# Sheet1.net
KiCad netlist of a schematic drawn in Altium Designer
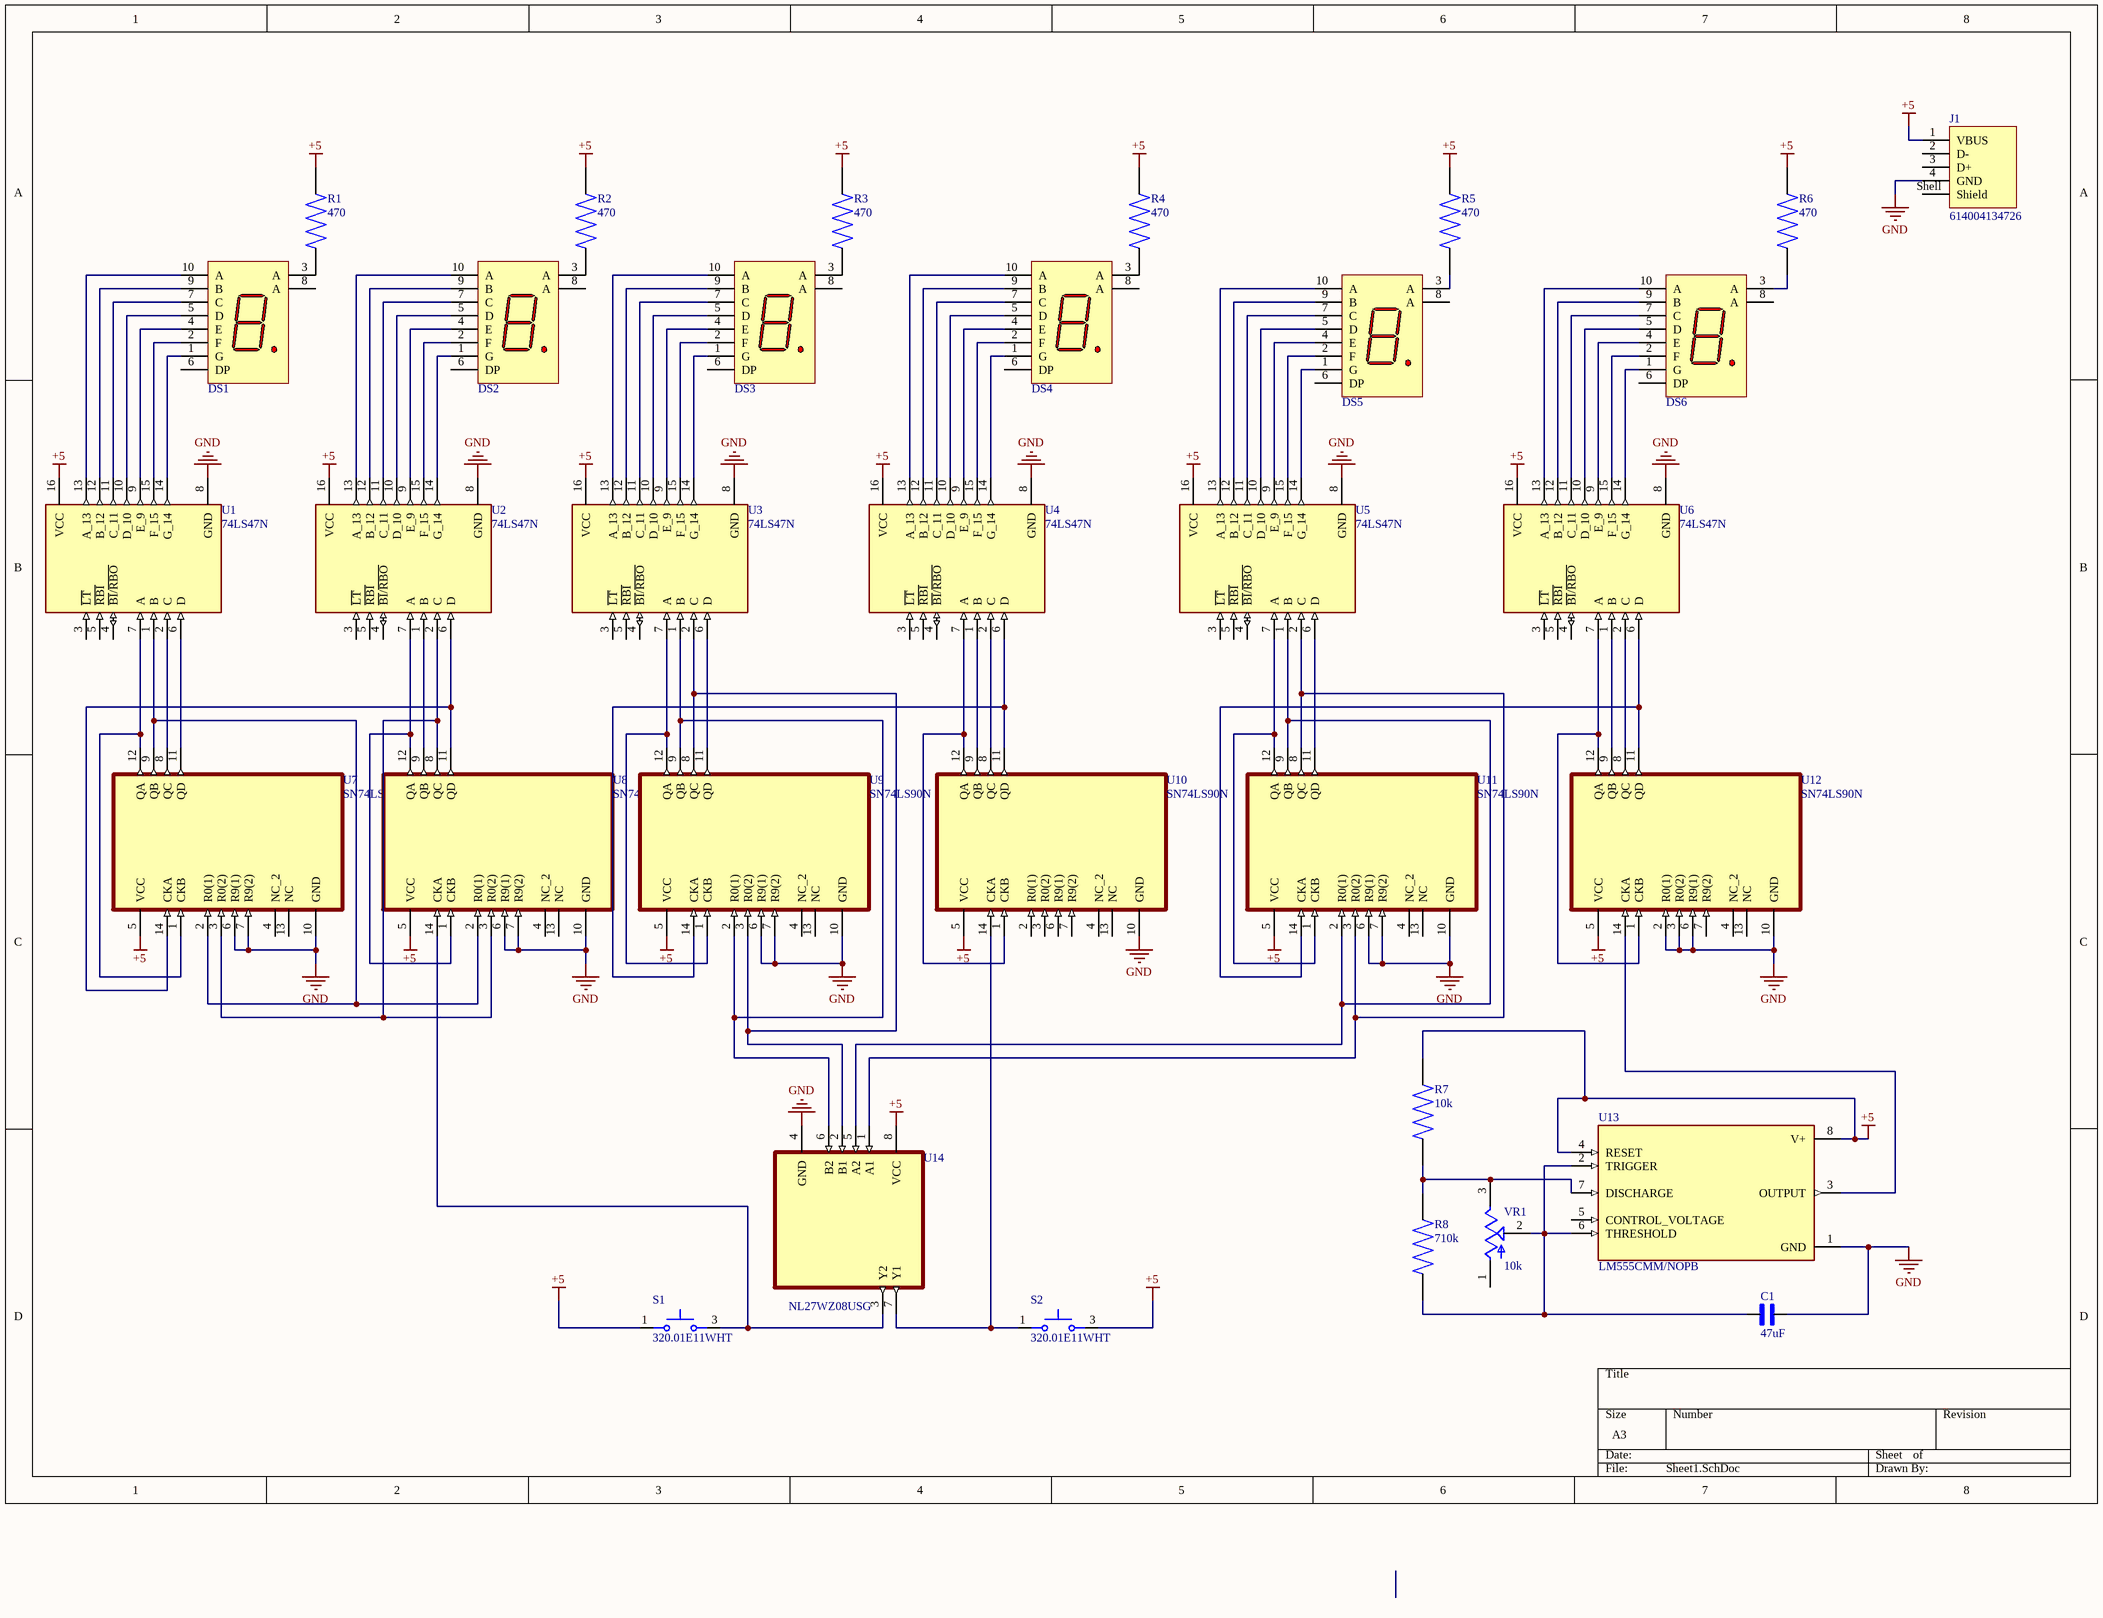
[diagram p0: Sheet1.SchDoc]

(export (version "E")
  (design (tool "Eeschema 10.0.6"))
  (components
    (comp (ref "C1")
      (value "47uF")
      (footprint "CAPC1608X90N")
      (description "Capacitor MLCC 0603 100nF 16V ¦ AVX 0603YC104KAZ2A")
      (fields (field (name "MF") "AVX") (field (name "MP") "0603YC104KAZ2A"))
      (libsource (lib "0603YC104KAZ2A") (part "0603YC104KAZ2A"))
    )
    (comp (ref "DS1")
      (value "157119S12801")
      (footprint "WL-T7DS_L13W10H7")
      (description "WL-T7DS 7 Segments Display THT Single Digit, 0.39\"/ 9.9mm, Common Anode, 38mcd, 2V, Super Red")
      (fields (field (name "MANUFACTURER") "Wurth Elektronik"))
      (libsource (lib "WL-T7DS") (part "157119S12801"))
    )
    (comp (ref "DS2")
      (value "157119S12801")
      (footprint "WL-T7DS_L13W10H7")
      (description "WL-T7DS 7 Segments Display THT Single Digit, 0.39\"/ 9.9mm, Common Anode, 38mcd, 2V, Super Red")
      (fields (field (name "MANUFACTURER") "Wurth Elektronik"))
      (libsource (lib "WL-T7DS") (part "157119S12801"))
    )
    (comp (ref "DS3")
      (value "157119S12801")
      (footprint "WL-T7DS_L13W10H7")
      (description "WL-T7DS 7 Segments Display THT Single Digit, 0.39\"/ 9.9mm, Common Anode, 38mcd, 2V, Super Red")
      (fields (field (name "MANUFACTURER") "Wurth Elektronik"))
      (libsource (lib "WL-T7DS") (part "157119S12801"))
    )
    (comp (ref "DS4")
      (value "157119S12801")
      (footprint "WL-T7DS_L13W10H7")
      (description "WL-T7DS 7 Segments Display THT Single Digit, 0.39\"/ 9.9mm, Common Anode, 38mcd, 2V, Super Red")
      (fields (field (name "MANUFACTURER") "Wurth Elektronik"))
      (libsource (lib "WL-T7DS") (part "157119S12801"))
    )
    (comp (ref "DS5")
      (value "157119S12801")
      (footprint "WL-T7DS_L13W10H7")
      (description "WL-T7DS 7 Segments Display THT Single Digit, 0.39\"/ 9.9mm, Common Anode, 38mcd, 2V, Super Red")
      (fields (field (name "MANUFACTURER") "Wurth Elektronik"))
      (libsource (lib "WL-T7DS") (part "157119S12801"))
    )
    (comp (ref "DS6")
      (value "157119S12801")
      (footprint "WL-T7DS_L13W10H7")
      (description "WL-T7DS 7 Segments Display THT Single Digit, 0.39\"/ 9.9mm, Common Anode, 38mcd, 2V, Super Red")
      (fields (field (name "MANUFACTURER") "Wurth Elektronik"))
      (libsource (lib "WL-T7DS") (part "157119S12801"))
    )
    (comp (ref "J1")
      (value "614004134726")
      (footprint "614004134726")
      (description "WR-COM USB 2.0 Type A Up Right")
      (fields (field (name "MANUFACTURER") "Wurth Elektronik"))
      (libsource (lib "WR-USB") (part "614004134726"))
    )
    (comp (ref "R1")
      (value "470")
      (footprint "RES_ERJU01F2202C:RES_ERJU01F2202C")
      (fields (field (name "MP") "ERJU01F2202C"))
      (libsource (lib "ERJU01F2202C") (part "ERJU01F2202C"))
    )
    (comp (ref "R2")
      (value "470")
      (footprint "RES_ERJU01F2202C:RES_ERJU01F2202C")
      (fields (field (name "MP") "ERJU01F2202C"))
      (libsource (lib "ERJU01F2202C") (part "ERJU01F2202C"))
    )
    (comp (ref "R3")
      (value "470")
      (footprint "RES_ERJU01F2202C:RES_ERJU01F2202C")
      (fields (field (name "MP") "ERJU01F2202C"))
      (libsource (lib "ERJU01F2202C") (part "ERJU01F2202C"))
    )
    (comp (ref "R4")
      (value "470")
      (footprint "RES_ERJU01F2202C:RES_ERJU01F2202C")
      (fields (field (name "MP") "ERJU01F2202C"))
      (libsource (lib "ERJU01F2202C") (part "ERJU01F2202C"))
    )
    (comp (ref "R5")
      (value "470")
      (footprint "RES_ERJU01F2202C:RES_ERJU01F2202C")
      (fields (field (name "MP") "ERJU01F2202C"))
      (libsource (lib "ERJU01F2202C") (part "ERJU01F2202C"))
    )
    (comp (ref "R6")
      (value "470")
      (footprint "RES_ERJU01F2202C:RES_ERJU01F2202C")
      (fields (field (name "MP") "ERJU01F2202C"))
      (libsource (lib "ERJU01F2202C") (part "ERJU01F2202C"))
    )
    (comp (ref "R7")
      (value "10k")
      (footprint "RES_ERJU01F2202C:RES_ERJU01F2202C")
      (fields (field (name "MP") "ERJU01F2202C"))
      (libsource (lib "ERJU01F2202C") (part "ERJU01F2202C"))
    )
    (comp (ref "R8")
      (value "710k")
      (footprint "RES_ERJU01F2202C:RES_ERJU01F2202C")
      (fields (field (name "MP") "ERJU01F2202C"))
      (libsource (lib "ERJU01F2202C") (part "ERJU01F2202C"))
    )
    (comp (ref "S1")
      (value "320.01E11WHT")
      (footprint "SW_320.01E11WHT")
      (description "PUSHBUTTON, 25mA, 50VDC SPST-NO, Off-(On) Through Hole")
      (fields (field (name "MF") "E-Switch"))
      (libsource (lib "320.01E11WHT") (part "320.01E11WHT"))
    )
    (comp (ref "S2")
      (value "320.01E11WHT")
      (footprint "SW_320.01E11WHT")
      (description "PUSHBUTTON, 25mA, 50VDC SPST-NO, Off-(On) Through Hole")
      (fields (field (name "MF") "E-Switch"))
      (libsource (lib "320.01E11WHT") (part "320.01E11WHT"))
    )
    (comp (ref "U1")
      (value "74LS47N")
      (footprint "DIP794W45P254L1930H508Q16")
      (description "IC DRVR BCD-7 SEGMENT 16SO")
      (fields (field (name "MF") "Texas Instruments"))
      (libsource (lib "74LS47N") (part "74LS47N"))
    )
    (comp (ref "U2")
      (value "74LS47N")
      (footprint "DIP794W45P254L1930H508Q16")
      (description "IC DRVR BCD-7 SEGMENT 16SO")
      (fields (field (name "MF") "Texas Instruments"))
      (libsource (lib "74LS47N") (part "74LS47N"))
    )
    (comp (ref "U3")
      (value "74LS47N")
      (footprint "DIP794W45P254L1930H508Q16")
      (description "IC DRVR BCD-7 SEGMENT 16SO")
      (fields (field (name "MF") "Texas Instruments"))
      (libsource (lib "74LS47N") (part "74LS47N"))
    )
    (comp (ref "U4")
      (value "74LS47N")
      (footprint "DIP794W45P254L1930H508Q16")
      (description "IC DRVR BCD-7 SEGMENT 16SO")
      (fields (field (name "MF") "Texas Instruments"))
      (libsource (lib "74LS47N") (part "74LS47N"))
    )
    (comp (ref "U5")
      (value "74LS47N")
      (footprint "DIP794W45P254L1930H508Q16")
      (description "IC DRVR BCD-7 SEGMENT 16SO")
      (fields (field (name "MF") "Texas Instruments"))
      (libsource (lib "74LS47N") (part "74LS47N"))
    )
    (comp (ref "U6")
      (value "74LS47N")
      (footprint "DIP794W45P254L1930H508Q16")
      (description "IC DRVR BCD-7 SEGMENT 16SO")
      (fields (field (name "MF") "Texas Instruments"))
      (libsource (lib "74LS47N") (part "74LS47N"))
    )
    (comp (ref "U7")
      (value "SN74LS90N")
      (footprint "DIP254P762X508-14")
      (description "Counter IC Counter, Decade 1 Element 4 Bit Negative Edge 14-SOIC")
      (fields (field (name "MF") "Texas Instruments") (field (name "MP") "74LS90"))
      (libsource (lib "SN74LS90N") (part "SN74LS90N"))
    )
    (comp (ref "U8")
      (value "SN74LS90N")
      (footprint "DIP254P762X508-14")
      (description "Counter IC Counter, Decade 1 Element 4 Bit Negative Edge 14-SOIC")
      (fields (field (name "MF") "Texas Instruments") (field (name "MP") "74LS90"))
      (libsource (lib "SN74LS90N") (part "SN74LS90N"))
    )
    (comp (ref "U9")
      (value "SN74LS90N")
      (footprint "DIP254P762X508-14")
      (description "Counter IC Counter, Decade 1 Element 4 Bit Negative Edge 14-SOIC")
      (fields (field (name "MF") "Texas Instruments") (field (name "MP") "74LS90"))
      (libsource (lib "SN74LS90N") (part "SN74LS90N"))
    )
    (comp (ref "U10")
      (value "SN74LS90N")
      (footprint "DIP254P762X508-14")
      (description "Counter IC Counter, Decade 1 Element 4 Bit Negative Edge 14-SOIC")
      (fields (field (name "MF") "Texas Instruments") (field (name "MP") "74LS90"))
      (libsource (lib "SN74LS90N") (part "SN74LS90N"))
    )
    (comp (ref "U11")
      (value "SN74LS90N")
      (footprint "DIP254P762X508-14")
      (description "Counter IC Counter, Decade 1 Element 4 Bit Negative Edge 14-SOIC")
      (fields (field (name "MF") "Texas Instruments") (field (name "MP") "74LS90"))
      (libsource (lib "SN74LS90N") (part "SN74LS90N"))
    )
    (comp (ref "U12")
      (value "SN74LS90N")
      (footprint "DIP254P762X508-14")
      (description "Counter IC Counter, Decade 1 Element 4 Bit Negative Edge 14-SOIC")
      (fields (field (name "MF") "Texas Instruments") (field (name "MP") "74LS90"))
      (libsource (lib "SN74LS90N") (part "SN74LS90N"))
    )
    (comp (ref "U13")
      (value "LM555CMM/NOPB")
      (footprint "SOP65P490X110-8N")
      (description "Highly Stable 555 Timer")
      (fields (field (name "MF") "Texas Instruments"))
      (libsource (lib "LM555CMM_NOPB") (part "LM555CMM/NOPB"))
    )
    (comp (ref "U14")
      (value "NL27WZ08USG")
      (footprint "SOP50P310X90-8N")
      (description "NL27WZ08USG, Dual 2-Input AND Logic Gate, 1.65 - 5.5 V, 8-Pin US ¦ ON Semiconductor NL27WZ08USG")
      (fields (field (name "MF") "ON Semiconductor"))
      (libsource (lib "NL27WZ08USG") (part "NL27WZ08USG"))
    )
    (comp (ref "VR1")
      (value "10k")
      (footprint "TRIM_3362P-1-223LF")
      (fields
        (field (name "MF") "Bourns Electronics")
        (field (name "MP") "3362P1223LF")
        (field (name "Comment") "3362P-1-223LF")
      )
      (libsource (lib "3362P-1-223LF") (part "3362P-1-223LF"))
    )
  )
  (nets
    (net (code "1") (name "+5") (class "Default")
      (node (ref "J1") (pin "1") (pinfunction "VBUS_1") (pintype "passive"))
      (node (ref "R1") (pin "2") (pinfunction "2_2") (pintype "passive"))
      (node (ref "R2") (pin "2") (pinfunction "2_2") (pintype "passive"))
      (node (ref "R3") (pin "2") (pinfunction "2_2") (pintype "passive"))
      (node (ref "R4") (pin "2") (pinfunction "2_2") (pintype "passive"))
      (node (ref "R5") (pin "2") (pinfunction "2_2") (pintype "passive"))
      (node (ref "R6") (pin "2") (pinfunction "2_2") (pintype "passive"))
      (node (ref "R7") (pin "2") (pinfunction "2_2") (pintype "passive"))
      (node (ref "S1") (pin "1") (pinfunction "1_1") (pintype "passive"))
      (node (ref "S2") (pin "3") (pinfunction "3_3") (pintype "passive"))
      (node (ref "U1") (pin "16") (pinfunction "VCC_16") (pintype "power_in"))
      (node (ref "U10") (pin "5") (pinfunction "VCC_5") (pintype "power_in"))
      (node (ref "U11") (pin "5") (pinfunction "VCC_5") (pintype "power_in"))
      (node (ref "U12") (pin "5") (pinfunction "VCC_5") (pintype "power_in"))
      (node (ref "U13") (pin "4") (pinfunction "RESET_4") (pintype "input"))
      (node (ref "U13") (pin "8") (pinfunction "V+_8") (pintype "power_in"))
      (node (ref "U14") (pin "8") (pinfunction "VCC_8") (pintype "power_in"))
      (node (ref "U2") (pin "16") (pinfunction "VCC_16") (pintype "power_in"))
      (node (ref "U3") (pin "16") (pinfunction "VCC_16") (pintype "power_in"))
      (node (ref "U4") (pin "16") (pinfunction "VCC_16") (pintype "power_in"))
      (node (ref "U5") (pin "16") (pinfunction "VCC_16") (pintype "power_in"))
      (node (ref "U6") (pin "16") (pinfunction "VCC_16") (pintype "power_in"))
      (node (ref "U7") (pin "5") (pinfunction "VCC_5") (pintype "power_in"))
      (node (ref "U8") (pin "5") (pinfunction "VCC_5") (pintype "power_in"))
      (node (ref "U9") (pin "5") (pinfunction "VCC_5") (pintype "power_in"))
    )
    (net (code "2") (name "GND") (class "Default")
      (node (ref "C1") (pin "2") (pinfunction "2_2") (pintype "passive"))
      (node (ref "J1") (pin "4") (pinfunction "GND_4") (pintype "passive"))
      (node (ref "U1") (pin "8") (pinfunction "GND_8") (pintype "power_in"))
      (node (ref "U10") (pin "10") (pinfunction "GND_10") (pintype "passive"))
      (node (ref "U11") (pin "10") (pinfunction "GND_10") (pintype "passive"))
      (node (ref "U11") (pin "6") (pinfunction "R9(1)_6") (pintype "input"))
      (node (ref "U11") (pin "7") (pinfunction "R9(2)_7") (pintype "input"))
      (node (ref "U12") (pin "10") (pinfunction "GND_10") (pintype "passive"))
      (node (ref "U12") (pin "2") (pinfunction "R0(1)_2") (pintype "input"))
      (node (ref "U12") (pin "3") (pinfunction "R0(2)_3") (pintype "input"))
      (node (ref "U12") (pin "6") (pinfunction "R9(1)_6") (pintype "input"))
      (node (ref "U13") (pin "1") (pinfunction "GND_1") (pintype "power_in"))
      (node (ref "U14") (pin "4") (pinfunction "GND_4") (pintype "passive"))
      (node (ref "U2") (pin "8") (pinfunction "GND_8") (pintype "power_in"))
      (node (ref "U3") (pin "8") (pinfunction "GND_8") (pintype "power_in"))
      (node (ref "U4") (pin "8") (pinfunction "GND_8") (pintype "power_in"))
      (node (ref "U5") (pin "8") (pinfunction "GND_8") (pintype "power_in"))
      (node (ref "U6") (pin "8") (pinfunction "GND_8") (pintype "power_in"))
      (node (ref "U7") (pin "10") (pinfunction "GND_10") (pintype "passive"))
      (node (ref "U7") (pin "6") (pinfunction "R9(1)_6") (pintype "input"))
      (node (ref "U7") (pin "7") (pinfunction "R9(2)_7") (pintype "input"))
      (node (ref "U8") (pin "10") (pinfunction "GND_10") (pintype "passive"))
      (node (ref "U8") (pin "6") (pinfunction "R9(1)_6") (pintype "input"))
      (node (ref "U8") (pin "7") (pinfunction "R9(2)_7") (pintype "input"))
      (node (ref "U9") (pin "10") (pinfunction "GND_10") (pintype "passive"))
      (node (ref "U9") (pin "6") (pinfunction "R9(1)_6") (pintype "input"))
      (node (ref "U9") (pin "7") (pinfunction "R9(2)_7") (pintype "input"))
    )
    (net (code "3") (name "Net-(DS1-A-Pad3)") (class "Default")
      (node (ref "DS1") (pin "3") (pinfunction "A_3") (pintype "passive"))
      (node (ref "R1") (pin "1") (pinfunction "1_1") (pintype "passive"))
    )
    (net (code "4") (name "Net-(DS1-B)") (class "Default")
      (node (ref "DS1") (pin "9") (pinfunction "B_9") (pintype "passive"))
      (node (ref "U1") (pin "12") (pinfunction "B_12_12") (pintype "output"))
    )
    (net (code "5") (name "Net-(DS1-C)") (class "Default")
      (node (ref "DS1") (pin "7") (pinfunction "C_7") (pintype "passive"))
      (node (ref "U1") (pin "11") (pinfunction "C_11_11") (pintype "output"))
    )
    (net (code "6") (name "Net-(DS1-D)") (class "Default")
      (node (ref "DS1") (pin "5") (pinfunction "D_5") (pintype "passive"))
      (node (ref "U1") (pin "10") (pinfunction "D_10_10") (pintype "output"))
    )
    (net (code "7") (name "Net-(DS1-E)") (class "Default")
      (node (ref "DS1") (pin "4") (pinfunction "E_4") (pintype "passive"))
      (node (ref "U1") (pin "9") (pinfunction "E_9_9") (pintype "output"))
    )
    (net (code "8") (name "Net-(DS1-F)") (class "Default")
      (node (ref "DS1") (pin "2") (pinfunction "F_2") (pintype "passive"))
      (node (ref "U1") (pin "15") (pinfunction "F_15_15") (pintype "output"))
    )
    (net (code "9") (name "Net-(DS1-G)") (class "Default")
      (node (ref "DS1") (pin "1") (pinfunction "G_1") (pintype "passive"))
      (node (ref "U1") (pin "14") (pinfunction "G_14_14") (pintype "output"))
    )
    (net (code "10") (name "Net-(DS2-A-Pad3)") (class "Default")
      (node (ref "DS2") (pin "3") (pinfunction "A_3") (pintype "passive"))
      (node (ref "R2") (pin "1") (pinfunction "1_1") (pintype "passive"))
    )
    (net (code "11") (name "Net-(DS2-B)") (class "Default")
      (node (ref "DS2") (pin "9") (pinfunction "B_9") (pintype "passive"))
      (node (ref "U2") (pin "12") (pinfunction "B_12_12") (pintype "output"))
    )
    (net (code "12") (name "Net-(DS2-C)") (class "Default")
      (node (ref "DS2") (pin "7") (pinfunction "C_7") (pintype "passive"))
      (node (ref "U2") (pin "11") (pinfunction "C_11_11") (pintype "output"))
    )
    (net (code "13") (name "Net-(DS2-D)") (class "Default")
      (node (ref "DS2") (pin "5") (pinfunction "D_5") (pintype "passive"))
      (node (ref "U2") (pin "10") (pinfunction "D_10_10") (pintype "output"))
    )
    (net (code "14") (name "Net-(DS2-E)") (class "Default")
      (node (ref "DS2") (pin "4") (pinfunction "E_4") (pintype "passive"))
      (node (ref "U2") (pin "9") (pinfunction "E_9_9") (pintype "output"))
    )
    (net (code "15") (name "Net-(DS2-F)") (class "Default")
      (node (ref "DS2") (pin "2") (pinfunction "F_2") (pintype "passive"))
      (node (ref "U2") (pin "15") (pinfunction "F_15_15") (pintype "output"))
    )
    (net (code "16") (name "Net-(DS2-G)") (class "Default")
      (node (ref "DS2") (pin "1") (pinfunction "G_1") (pintype "passive"))
      (node (ref "U2") (pin "14") (pinfunction "G_14_14") (pintype "output"))
    )
    (net (code "17") (name "Net-(DS3-A-Pad3)") (class "Default")
      (node (ref "DS3") (pin "3") (pinfunction "A_3") (pintype "passive"))
      (node (ref "R3") (pin "1") (pinfunction "1_1") (pintype "passive"))
    )
    (net (code "18") (name "Net-(DS3-B)") (class "Default")
      (node (ref "DS3") (pin "9") (pinfunction "B_9") (pintype "passive"))
      (node (ref "U3") (pin "12") (pinfunction "B_12_12") (pintype "output"))
    )
    (net (code "19") (name "Net-(DS3-C)") (class "Default")
      (node (ref "DS3") (pin "7") (pinfunction "C_7") (pintype "passive"))
      (node (ref "U3") (pin "11") (pinfunction "C_11_11") (pintype "output"))
    )
    (net (code "20") (name "Net-(DS3-D)") (class "Default")
      (node (ref "DS3") (pin "5") (pinfunction "D_5") (pintype "passive"))
      (node (ref "U3") (pin "10") (pinfunction "D_10_10") (pintype "output"))
    )
    (net (code "21") (name "Net-(DS3-E)") (class "Default")
      (node (ref "DS3") (pin "4") (pinfunction "E_4") (pintype "passive"))
      (node (ref "U3") (pin "9") (pinfunction "E_9_9") (pintype "output"))
    )
    (net (code "22") (name "Net-(DS3-F)") (class "Default")
      (node (ref "DS3") (pin "2") (pinfunction "F_2") (pintype "passive"))
      (node (ref "U3") (pin "15") (pinfunction "F_15_15") (pintype "output"))
    )
    (net (code "23") (name "Net-(DS3-G)") (class "Default")
      (node (ref "DS3") (pin "1") (pinfunction "G_1") (pintype "passive"))
      (node (ref "U3") (pin "14") (pinfunction "G_14_14") (pintype "output"))
    )
    (net (code "24") (name "Net-(DS4-A-Pad3)") (class "Default")
      (node (ref "DS4") (pin "3") (pinfunction "A_3") (pintype "passive"))
      (node (ref "R4") (pin "1") (pinfunction "1_1") (pintype "passive"))
    )
    (net (code "25") (name "Net-(DS4-B)") (class "Default")
      (node (ref "DS4") (pin "9") (pinfunction "B_9") (pintype "passive"))
      (node (ref "U4") (pin "12") (pinfunction "B_12_12") (pintype "output"))
    )
    (net (code "26") (name "Net-(DS4-C)") (class "Default")
      (node (ref "DS4") (pin "7") (pinfunction "C_7") (pintype "passive"))
      (node (ref "U4") (pin "11") (pinfunction "C_11_11") (pintype "output"))
    )
    (net (code "27") (name "Net-(DS4-D)") (class "Default")
      (node (ref "DS4") (pin "5") (pinfunction "D_5") (pintype "passive"))
      (node (ref "U4") (pin "10") (pinfunction "D_10_10") (pintype "output"))
    )
    (net (code "28") (name "Net-(DS4-E)") (class "Default")
      (node (ref "DS4") (pin "4") (pinfunction "E_4") (pintype "passive"))
      (node (ref "U4") (pin "9") (pinfunction "E_9_9") (pintype "output"))
    )
    (net (code "29") (name "Net-(DS4-F)") (class "Default")
      (node (ref "DS4") (pin "2") (pinfunction "F_2") (pintype "passive"))
      (node (ref "U4") (pin "15") (pinfunction "F_15_15") (pintype "output"))
    )
    (net (code "30") (name "Net-(DS4-G)") (class "Default")
      (node (ref "DS4") (pin "1") (pinfunction "G_1") (pintype "passive"))
      (node (ref "U4") (pin "14") (pinfunction "G_14_14") (pintype "output"))
    )
    (net (code "31") (name "Net-(DS5-A-Pad3)") (class "Default")
      (node (ref "DS5") (pin "3") (pinfunction "A_3") (pintype "passive"))
      (node (ref "R5") (pin "1") (pinfunction "1_1") (pintype "passive"))
    )
    (net (code "32") (name "Net-(DS5-B)") (class "Default")
      (node (ref "DS5") (pin "9") (pinfunction "B_9") (pintype "passive"))
      (node (ref "U5") (pin "12") (pinfunction "B_12_12") (pintype "output"))
    )
    (net (code "33") (name "Net-(DS5-C)") (class "Default")
      (node (ref "DS5") (pin "7") (pinfunction "C_7") (pintype "passive"))
      (node (ref "U5") (pin "11") (pinfunction "C_11_11") (pintype "output"))
    )
    (net (code "34") (name "Net-(DS5-D)") (class "Default")
      (node (ref "DS5") (pin "5") (pinfunction "D_5") (pintype "passive"))
      (node (ref "U5") (pin "10") (pinfunction "D_10_10") (pintype "output"))
    )
    (net (code "35") (name "Net-(DS5-E)") (class "Default")
      (node (ref "DS5") (pin "4") (pinfunction "E_4") (pintype "passive"))
      (node (ref "U5") (pin "9") (pinfunction "E_9_9") (pintype "output"))
    )
    (net (code "36") (name "Net-(DS5-F)") (class "Default")
      (node (ref "DS5") (pin "2") (pinfunction "F_2") (pintype "passive"))
      (node (ref "U5") (pin "15") (pinfunction "F_15_15") (pintype "output"))
    )
    (net (code "37") (name "Net-(DS5-G)") (class "Default")
      (node (ref "DS5") (pin "1") (pinfunction "G_1") (pintype "passive"))
      (node (ref "U5") (pin "14") (pinfunction "G_14_14") (pintype "output"))
    )
    (net (code "38") (name "Net-(DS6-A-Pad3)") (class "Default")
      (node (ref "DS6") (pin "3") (pinfunction "A_3") (pintype "passive"))
      (node (ref "R6") (pin "1") (pinfunction "1_1") (pintype "passive"))
    )
    (net (code "39") (name "Net-(DS6-B)") (class "Default")
      (node (ref "DS6") (pin "9") (pinfunction "B_9") (pintype "passive"))
      (node (ref "U6") (pin "12") (pinfunction "B_12_12") (pintype "output"))
    )
    (net (code "40") (name "Net-(DS6-C)") (class "Default")
      (node (ref "DS6") (pin "7") (pinfunction "C_7") (pintype "passive"))
      (node (ref "U6") (pin "11") (pinfunction "C_11_11") (pintype "output"))
    )
    (net (code "41") (name "Net-(DS6-D)") (class "Default")
      (node (ref "DS6") (pin "5") (pinfunction "D_5") (pintype "passive"))
      (node (ref "U6") (pin "10") (pinfunction "D_10_10") (pintype "output"))
    )
    (net (code "42") (name "Net-(DS6-E)") (class "Default")
      (node (ref "DS6") (pin "4") (pinfunction "E_4") (pintype "passive"))
      (node (ref "U6") (pin "9") (pinfunction "E_9_9") (pintype "output"))
    )
    (net (code "43") (name "Net-(DS6-F)") (class "Default")
      (node (ref "DS6") (pin "2") (pinfunction "F_2") (pintype "passive"))
      (node (ref "U6") (pin "15") (pinfunction "F_15_15") (pintype "output"))
    )
    (net (code "44") (name "Net-(DS6-G)") (class "Default")
      (node (ref "DS6") (pin "1") (pinfunction "G_1") (pintype "passive"))
      (node (ref "U6") (pin "14") (pinfunction "G_14_14") (pintype "output"))
    )
    (net (code "45") (name "Net-(U1-A)") (class "Default")
      (node (ref "U1") (pin "7") (pinfunction "A_7") (pintype "input"))
      (node (ref "U7") (pin "1") (pinfunction "CKB_1") (pintype "input"))
      (node (ref "U7") (pin "12") (pinfunction "QA_12") (pintype "output"))
    )
    (net (code "46") (name "Net-(U1-A_13)") (class "Default")
      (node (ref "DS1") (pin "10") (pinfunction "A_10") (pintype "passive"))
      (node (ref "U1") (pin "13") (pinfunction "A_13_13") (pintype "output"))
    )
    (net (code "47") (name "Net-(U1-B)") (class "Default")
      (node (ref "U1") (pin "1") (pinfunction "B_1") (pintype "input"))
      (node (ref "U7") (pin "2") (pinfunction "R0(1)_2") (pintype "input"))
      (node (ref "U7") (pin "9") (pinfunction "QB_9") (pintype "output"))
      (node (ref "U8") (pin "2") (pinfunction "R0(1)_2") (pintype "input"))
    )
    (net (code "48") (name "Net-(U1-C)") (class "Default")
      (node (ref "U1") (pin "2") (pinfunction "C_2") (pintype "input"))
      (node (ref "U7") (pin "8") (pinfunction "QC_8") (pintype "output"))
    )
    (net (code "49") (name "Net-(U1-D)") (class "Default")
      (node (ref "U1") (pin "6") (pinfunction "D_6") (pintype "input"))
      (node (ref "U7") (pin "11") (pinfunction "QD_11") (pintype "output"))
    )
    (net (code "50") (name "Net-(U2-A)") (class "Default")
      (node (ref "U2") (pin "7") (pinfunction "A_7") (pintype "input"))
      (node (ref "U8") (pin "1") (pinfunction "CKB_1") (pintype "input"))
      (node (ref "U8") (pin "12") (pinfunction "QA_12") (pintype "output"))
    )
    (net (code "51") (name "Net-(U2-A_13)") (class "Default")
      (node (ref "DS2") (pin "10") (pinfunction "A_10") (pintype "passive"))
      (node (ref "U2") (pin "13") (pinfunction "A_13_13") (pintype "output"))
    )
    (net (code "52") (name "Net-(U2-B)") (class "Default")
      (node (ref "U2") (pin "1") (pinfunction "B_1") (pintype "input"))
      (node (ref "U8") (pin "9") (pinfunction "QB_9") (pintype "output"))
    )
    (net (code "53") (name "Net-(U2-C)") (class "Default")
      (node (ref "U2") (pin "2") (pinfunction "C_2") (pintype "input"))
      (node (ref "U7") (pin "3") (pinfunction "R0(2)_3") (pintype "input"))
      (node (ref "U8") (pin "3") (pinfunction "R0(2)_3") (pintype "input"))
      (node (ref "U8") (pin "8") (pinfunction "QC_8") (pintype "output"))
    )
    (net (code "54") (name "Net-(U2-D)") (class "Default")
      (node (ref "U2") (pin "6") (pinfunction "D_6") (pintype "input"))
      (node (ref "U7") (pin "14") (pinfunction "CKA_14") (pintype "input"))
      (node (ref "U8") (pin "11") (pinfunction "QD_11") (pintype "output"))
    )
    (net (code "55") (name "Net-(U3-A)") (class "Default")
      (node (ref "U3") (pin "7") (pinfunction "A_7") (pintype "input"))
      (node (ref "U9") (pin "1") (pinfunction "CKB_1") (pintype "input"))
      (node (ref "U9") (pin "12") (pinfunction "QA_12") (pintype "output"))
    )
    (net (code "56") (name "Net-(U3-A_13)") (class "Default")
      (node (ref "DS3") (pin "10") (pinfunction "A_10") (pintype "passive"))
      (node (ref "U3") (pin "13") (pinfunction "A_13_13") (pintype "output"))
    )
    (net (code "57") (name "Net-(U3-D)") (class "Default")
      (node (ref "U3") (pin "6") (pinfunction "D_6") (pintype "input"))
      (node (ref "U9") (pin "11") (pinfunction "QD_11") (pintype "output"))
    )
    (net (code "58") (name "Net-(U4-A_13)") (class "Default")
      (node (ref "DS4") (pin "10") (pinfunction "A_10") (pintype "passive"))
      (node (ref "U4") (pin "13") (pinfunction "A_13_13") (pintype "output"))
    )
    (net (code "59") (name "Net-(U5-A_13)") (class "Default")
      (node (ref "DS5") (pin "10") (pinfunction "A_10") (pintype "passive"))
      (node (ref "U5") (pin "13") (pinfunction "A_13_13") (pintype "output"))
    )
    (net (code "60") (name "Net-(U6-A_13)") (class "Default")
      (node (ref "DS6") (pin "10") (pinfunction "A_10") (pintype "passive"))
      (node (ref "U6") (pin "13") (pinfunction "A_13_13") (pintype "output"))
    )
    (net (code "61") (name "Net-(U10-CKA)") (class "Default")
      (node (ref "S2") (pin "1") (pinfunction "1_1") (pintype "passive"))
      (node (ref "U10") (pin "14") (pinfunction "CKA_14") (pintype "input"))
      (node (ref "U14") (pin "7") (pinfunction "Y1_7") (pintype "output"))
    )
    (net (code "62") (name "Net-(U10-CKB)") (class "Default")
      (node (ref "U10") (pin "1") (pinfunction "CKB_1") (pintype "input"))
      (node (ref "U10") (pin "12") (pinfunction "QA_12") (pintype "output"))
      (node (ref "U4") (pin "7") (pinfunction "A_7") (pintype "input"))
    )
    (net (code "63") (name "Net-(U10-QB)") (class "Default")
      (node (ref "U10") (pin "9") (pinfunction "QB_9") (pintype "output"))
      (node (ref "U4") (pin "1") (pinfunction "B_1") (pintype "input"))
    )
    (net (code "64") (name "Net-(U10-QC)") (class "Default")
      (node (ref "U10") (pin "8") (pinfunction "QC_8") (pintype "output"))
      (node (ref "U4") (pin "2") (pinfunction "C_2") (pintype "input"))
    )
    (net (code "65") (name "Net-(U10-QD)") (class "Default")
      (node (ref "U10") (pin "11") (pinfunction "QD_11") (pintype "output"))
      (node (ref "U4") (pin "6") (pinfunction "D_6") (pintype "input"))
      (node (ref "U9") (pin "14") (pinfunction "CKA_14") (pintype "input"))
    )
    (net (code "66") (name "Net-(U11-CKA)") (class "Default")
      (node (ref "U11") (pin "14") (pinfunction "CKA_14") (pintype "input"))
      (node (ref "U12") (pin "11") (pinfunction "QD_11") (pintype "output"))
      (node (ref "U6") (pin "6") (pinfunction "D_6") (pintype "input"))
    )
    (net (code "67") (name "Net-(U11-CKB)") (class "Default")
      (node (ref "U11") (pin "1") (pinfunction "CKB_1") (pintype "input"))
      (node (ref "U11") (pin "12") (pinfunction "QA_12") (pintype "output"))
      (node (ref "U5") (pin "7") (pinfunction "A_7") (pintype "input"))
    )
    (net (code "68") (name "Net-(U11-QB)") (class "Default")
      (node (ref "U11") (pin "2") (pinfunction "R0(1)_2") (pintype "input"))
      (node (ref "U11") (pin "9") (pinfunction "QB_9") (pintype "output"))
      (node (ref "U14") (pin "5") (pinfunction "A2_5") (pintype "input"))
      (node (ref "U5") (pin "1") (pinfunction "B_1") (pintype "input"))
    )
    (net (code "69") (name "Net-(U11-QC)") (class "Default")
      (node (ref "U11") (pin "3") (pinfunction "R0(2)_3") (pintype "input"))
      (node (ref "U11") (pin "8") (pinfunction "QC_8") (pintype "output"))
      (node (ref "U14") (pin "1") (pinfunction "A1_1") (pintype "input"))
      (node (ref "U5") (pin "2") (pinfunction "C_2") (pintype "input"))
    )
    (net (code "70") (name "Net-(U11-QD)") (class "Default")
      (node (ref "U11") (pin "11") (pinfunction "QD_11") (pintype "output"))
      (node (ref "U5") (pin "6") (pinfunction "D_6") (pintype "input"))
    )
    (net (code "71") (name "Net-(U12-CKA)") (class "Default")
      (node (ref "U12") (pin "14") (pinfunction "CKA_14") (pintype "input"))
      (node (ref "U13") (pin "3") (pinfunction "OUTPUT_3") (pintype "output"))
    )
    (net (code "72") (name "Net-(U12-CKB)") (class "Default")
      (node (ref "U12") (pin "1") (pinfunction "CKB_1") (pintype "input"))
      (node (ref "U12") (pin "12") (pinfunction "QA_12") (pintype "output"))
      (node (ref "U6") (pin "7") (pinfunction "A_7") (pintype "input"))
    )
    (net (code "73") (name "Net-(U12-QB)") (class "Default")
      (node (ref "U12") (pin "9") (pinfunction "QB_9") (pintype "output"))
      (node (ref "U6") (pin "1") (pinfunction "B_1") (pintype "input"))
    )
    (net (code "74") (name "Net-(U12-QC)") (class "Default")
      (node (ref "U12") (pin "8") (pinfunction "QC_8") (pintype "output"))
      (node (ref "U6") (pin "2") (pinfunction "C_2") (pintype "input"))
    )
    (net (code "75") (name "Net-(U13-DISCHARGE)") (class "Default")
      (node (ref "R7") (pin "1") (pinfunction "1_1") (pintype "passive"))
      (node (ref "R8") (pin "2") (pinfunction "2_2") (pintype "passive"))
      (node (ref "U13") (pin "7") (pinfunction "DISCHARGE_7") (pintype "input"))
      (node (ref "VR1") (pin "3") (pinfunction "CW_3") (pintype "passive"))
    )
    (net (code "76") (name "Net-(U13-THRESHOLD)") (class "Default")
      (node (ref "C1") (pin "1") (pinfunction "1_1") (pintype "passive"))
      (node (ref "R8") (pin "1") (pinfunction "1_1") (pintype "passive"))
      (node (ref "U13") (pin "2") (pinfunction "TRIGGER_2") (pintype "input"))
      (node (ref "U13") (pin "6") (pinfunction "THRESHOLD_6") (pintype "input"))
      (node (ref "VR1") (pin "2") (pinfunction "WIPER_2") (pintype "passive"))
    )
    (net (code "77") (name "Net-(U14-B1)") (class "Default")
      (node (ref "U14") (pin "2") (pinfunction "B1_2") (pintype "input"))
      (node (ref "U3") (pin "2") (pinfunction "C_2") (pintype "input"))
      (node (ref "U9") (pin "3") (pinfunction "R0(2)_3") (pintype "input"))
      (node (ref "U9") (pin "8") (pinfunction "QC_8") (pintype "output"))
    )
    (net (code "78") (name "Net-(U14-B2)") (class "Default")
      (node (ref "U14") (pin "6") (pinfunction "B2_6") (pintype "input"))
      (node (ref "U3") (pin "1") (pinfunction "B_1") (pintype "input"))
      (node (ref "U9") (pin "2") (pinfunction "R0(1)_2") (pintype "input"))
      (node (ref "U9") (pin "9") (pinfunction "QB_9") (pintype "output"))
    )
    (net (code "79") (name "Net-(U14-Y2)") (class "Default")
      (node (ref "S1") (pin "3") (pinfunction "3_3") (pintype "passive"))
      (node (ref "U14") (pin "3") (pinfunction "Y2_3") (pintype "output"))
      (node (ref "U8") (pin "14") (pinfunction "CKA_14") (pintype "input"))
    )
    (net (code "80") (name "unconnected-(DS1-A-Pad8)") (class "Default")
      (node (ref "DS1") (pin "8") (pinfunction "A_8") (pintype "passive"))
    )
    (net (code "81") (name "unconnected-(DS1-DP-Pad6)") (class "Default")
      (node (ref "DS1") (pin "6") (pinfunction "DP_6") (pintype "passive"))
    )
    (net (code "82") (name "unconnected-(DS2-A-Pad8)") (class "Default")
      (node (ref "DS2") (pin "8") (pinfunction "A_8") (pintype "passive"))
    )
    (net (code "83") (name "unconnected-(DS2-DP-Pad6)") (class "Default")
      (node (ref "DS2") (pin "6") (pinfunction "DP_6") (pintype "passive"))
    )
    (net (code "84") (name "unconnected-(DS3-A-Pad8)") (class "Default")
      (node (ref "DS3") (pin "8") (pinfunction "A_8") (pintype "passive"))
    )
    (net (code "85") (name "unconnected-(DS3-DP-Pad6)") (class "Default")
      (node (ref "DS3") (pin "6") (pinfunction "DP_6") (pintype "passive"))
    )
    (net (code "86") (name "unconnected-(DS4-A-Pad8)") (class "Default")
      (node (ref "DS4") (pin "8") (pinfunction "A_8") (pintype "passive"))
    )
    (net (code "87") (name "unconnected-(DS4-DP-Pad6)") (class "Default")
      (node (ref "DS4") (pin "6") (pinfunction "DP_6") (pintype "passive"))
    )
    (net (code "88") (name "unconnected-(DS5-A-Pad8)") (class "Default")
      (node (ref "DS5") (pin "8") (pinfunction "A_8") (pintype "passive"))
    )
    (net (code "89") (name "unconnected-(DS5-DP-Pad6)") (class "Default")
      (node (ref "DS5") (pin "6") (pinfunction "DP_6") (pintype "passive"))
    )
    (net (code "90") (name "unconnected-(DS6-A-Pad8)") (class "Default")
      (node (ref "DS6") (pin "8") (pinfunction "A_8") (pintype "passive"))
    )
    (net (code "91") (name "unconnected-(DS6-DP-Pad6)") (class "Default")
      (node (ref "DS6") (pin "6") (pinfunction "DP_6") (pintype "passive"))
    )
    (net (code "92") (name "unconnected-(J1-D+-Pad3)") (class "Default")
      (node (ref "J1") (pin "3") (pinfunction "D+_3") (pintype "passive"))
    )
    (net (code "93") (name "unconnected-(J1-D--Pad2)") (class "Default")
      (node (ref "J1") (pin "2") (pinfunction "D-_2") (pintype "passive"))
    )
    (net (code "94") (name "unconnected-(J1-Shield-PadShell)") (class "Default")
      (node (ref "J1") (pin "Shell") (pinfunction "Shield_Shell") (pintype "passive"))
    )
    (net (code "95") (name "unconnected-(U1-~{BI}{slash}~{RBO}-Pad4)") (class "Default")
      (node (ref "U1") (pin "4") (pinfunction "~{BI}/~{RBO}_4") (pintype "bidirectional"))
    )
    (net (code "96") (name "unconnected-(U1-~{LT}-Pad3)") (class "Default")
      (node (ref "U1") (pin "3") (pinfunction "~{LT}_3") (pintype "input"))
    )
    (net (code "97") (name "unconnected-(U1-~{RBI}-Pad5)") (class "Default")
      (node (ref "U1") (pin "5") (pinfunction "~{RBI}_5") (pintype "input"))
    )
    (net (code "98") (name "unconnected-(U2-~{BI}{slash}~{RBO}-Pad4)") (class "Default")
      (node (ref "U2") (pin "4") (pinfunction "~{BI}/~{RBO}_4") (pintype "bidirectional"))
    )
    (net (code "99") (name "unconnected-(U2-~{LT}-Pad3)") (class "Default")
      (node (ref "U2") (pin "3") (pinfunction "~{LT}_3") (pintype "input"))
    )
    (net (code "100") (name "unconnected-(U2-~{RBI}-Pad5)") (class "Default")
      (node (ref "U2") (pin "5") (pinfunction "~{RBI}_5") (pintype "input"))
    )
    (net (code "101") (name "unconnected-(U3-~{BI}{slash}~{RBO}-Pad4)") (class "Default")
      (node (ref "U3") (pin "4") (pinfunction "~{BI}/~{RBO}_4") (pintype "bidirectional"))
    )
    (net (code "102") (name "unconnected-(U3-~{LT}-Pad3)") (class "Default")
      (node (ref "U3") (pin "3") (pinfunction "~{LT}_3") (pintype "input"))
    )
    (net (code "103") (name "unconnected-(U3-~{RBI}-Pad5)") (class "Default")
      (node (ref "U3") (pin "5") (pinfunction "~{RBI}_5") (pintype "input"))
    )
    (net (code "104") (name "unconnected-(U4-~{BI}{slash}~{RBO}-Pad4)") (class "Default")
      (node (ref "U4") (pin "4") (pinfunction "~{BI}/~{RBO}_4") (pintype "bidirectional"))
    )
    (net (code "105") (name "unconnected-(U4-~{LT}-Pad3)") (class "Default")
      (node (ref "U4") (pin "3") (pinfunction "~{LT}_3") (pintype "input"))
    )
    (net (code "106") (name "unconnected-(U4-~{RBI}-Pad5)") (class "Default")
      (node (ref "U4") (pin "5") (pinfunction "~{RBI}_5") (pintype "input"))
    )
    (net (code "107") (name "unconnected-(U5-~{BI}{slash}~{RBO}-Pad4)") (class "Default")
      (node (ref "U5") (pin "4") (pinfunction "~{BI}/~{RBO}_4") (pintype "bidirectional"))
    )
    (net (code "108") (name "unconnected-(U5-~{LT}-Pad3)") (class "Default")
      (node (ref "U5") (pin "3") (pinfunction "~{LT}_3") (pintype "input"))
    )
    (net (code "109") (name "unconnected-(U5-~{RBI}-Pad5)") (class "Default")
      (node (ref "U5") (pin "5") (pinfunction "~{RBI}_5") (pintype "input"))
    )
    (net (code "110") (name "unconnected-(U6-~{BI}{slash}~{RBO}-Pad4)") (class "Default")
      (node (ref "U6") (pin "4") (pinfunction "~{BI}/~{RBO}_4") (pintype "bidirectional"))
    )
    (net (code "111") (name "unconnected-(U6-~{LT}-Pad3)") (class "Default")
      (node (ref "U6") (pin "3") (pinfunction "~{LT}_3") (pintype "input"))
    )
    (net (code "112") (name "unconnected-(U6-~{RBI}-Pad5)") (class "Default")
      (node (ref "U6") (pin "5") (pinfunction "~{RBI}_5") (pintype "input"))
    )
    (net (code "113") (name "unconnected-(U7-NC-Pad13)") (class "Default")
      (node (ref "U7") (pin "13") (pinfunction "NC_13") (pintype "passive"))
    )
    (net (code "114") (name "unconnected-(U7-NC_2-Pad4)") (class "Default")
      (node (ref "U7") (pin "4") (pinfunction "NC_2_4") (pintype "passive"))
    )
    (net (code "115") (name "unconnected-(U8-NC-Pad13)") (class "Default")
      (node (ref "U8") (pin "13") (pinfunction "NC_13") (pintype "passive"))
    )
    (net (code "116") (name "unconnected-(U8-NC_2-Pad4)") (class "Default")
      (node (ref "U8") (pin "4") (pinfunction "NC_2_4") (pintype "passive"))
    )
    (net (code "117") (name "unconnected-(U9-NC-Pad13)") (class "Default")
      (node (ref "U9") (pin "13") (pinfunction "NC_13") (pintype "passive"))
    )
    (net (code "118") (name "unconnected-(U9-NC_2-Pad4)") (class "Default")
      (node (ref "U9") (pin "4") (pinfunction "NC_2_4") (pintype "passive"))
    )
    (net (code "119") (name "unconnected-(U10-NC-Pad13)") (class "Default")
      (node (ref "U10") (pin "13") (pinfunction "NC_13") (pintype "passive"))
    )
    (net (code "120") (name "unconnected-(U10-NC_2-Pad4)") (class "Default")
      (node (ref "U10") (pin "4") (pinfunction "NC_2_4") (pintype "passive"))
    )
    (net (code "121") (name "unconnected-(U10-R0(1)-Pad2)") (class "Default")
      (node (ref "U10") (pin "2") (pinfunction "R0(1)_2") (pintype "input"))
    )
    (net (code "122") (name "unconnected-(U10-R0(2)-Pad3)") (class "Default")
      (node (ref "U10") (pin "3") (pinfunction "R0(2)_3") (pintype "input"))
    )
    (net (code "123") (name "unconnected-(U10-R9(1)-Pad6)") (class "Default")
      (node (ref "U10") (pin "6") (pinfunction "R9(1)_6") (pintype "input"))
    )
    (net (code "124") (name "unconnected-(U10-R9(2)-Pad7)") (class "Default")
      (node (ref "U10") (pin "7") (pinfunction "R9(2)_7") (pintype "input"))
    )
    (net (code "125") (name "unconnected-(U11-NC-Pad13)") (class "Default")
      (node (ref "U11") (pin "13") (pinfunction "NC_13") (pintype "passive"))
    )
    (net (code "126") (name "unconnected-(U11-NC_2-Pad4)") (class "Default")
      (node (ref "U11") (pin "4") (pinfunction "NC_2_4") (pintype "passive"))
    )
    (net (code "127") (name "unconnected-(U12-NC-Pad13)") (class "Default")
      (node (ref "U12") (pin "13") (pinfunction "NC_13") (pintype "passive"))
    )
    (net (code "128") (name "unconnected-(U12-NC_2-Pad4)") (class "Default")
      (node (ref "U12") (pin "4") (pinfunction "NC_2_4") (pintype "passive"))
    )
    (net (code "129") (name "unconnected-(U12-R9(2)-Pad7)") (class "Default")
      (node (ref "U12") (pin "7") (pinfunction "R9(2)_7") (pintype "input"))
    )
    (net (code "130") (name "unconnected-(U13-CONTROL_VOLTAGE-Pad5)") (class "Default")
      (node (ref "U13") (pin "5") (pinfunction "CONTROL_VOLTAGE_5") (pintype "input"))
    )
    (net (code "131") (name "unconnected-(VR1-CCW-Pad1)") (class "Default")
      (node (ref "VR1") (pin "1") (pinfunction "CCW_1") (pintype "passive"))
    )
  )
)
